# main_board.net
KiCad netlist of a schematic drawn in Altium Designer
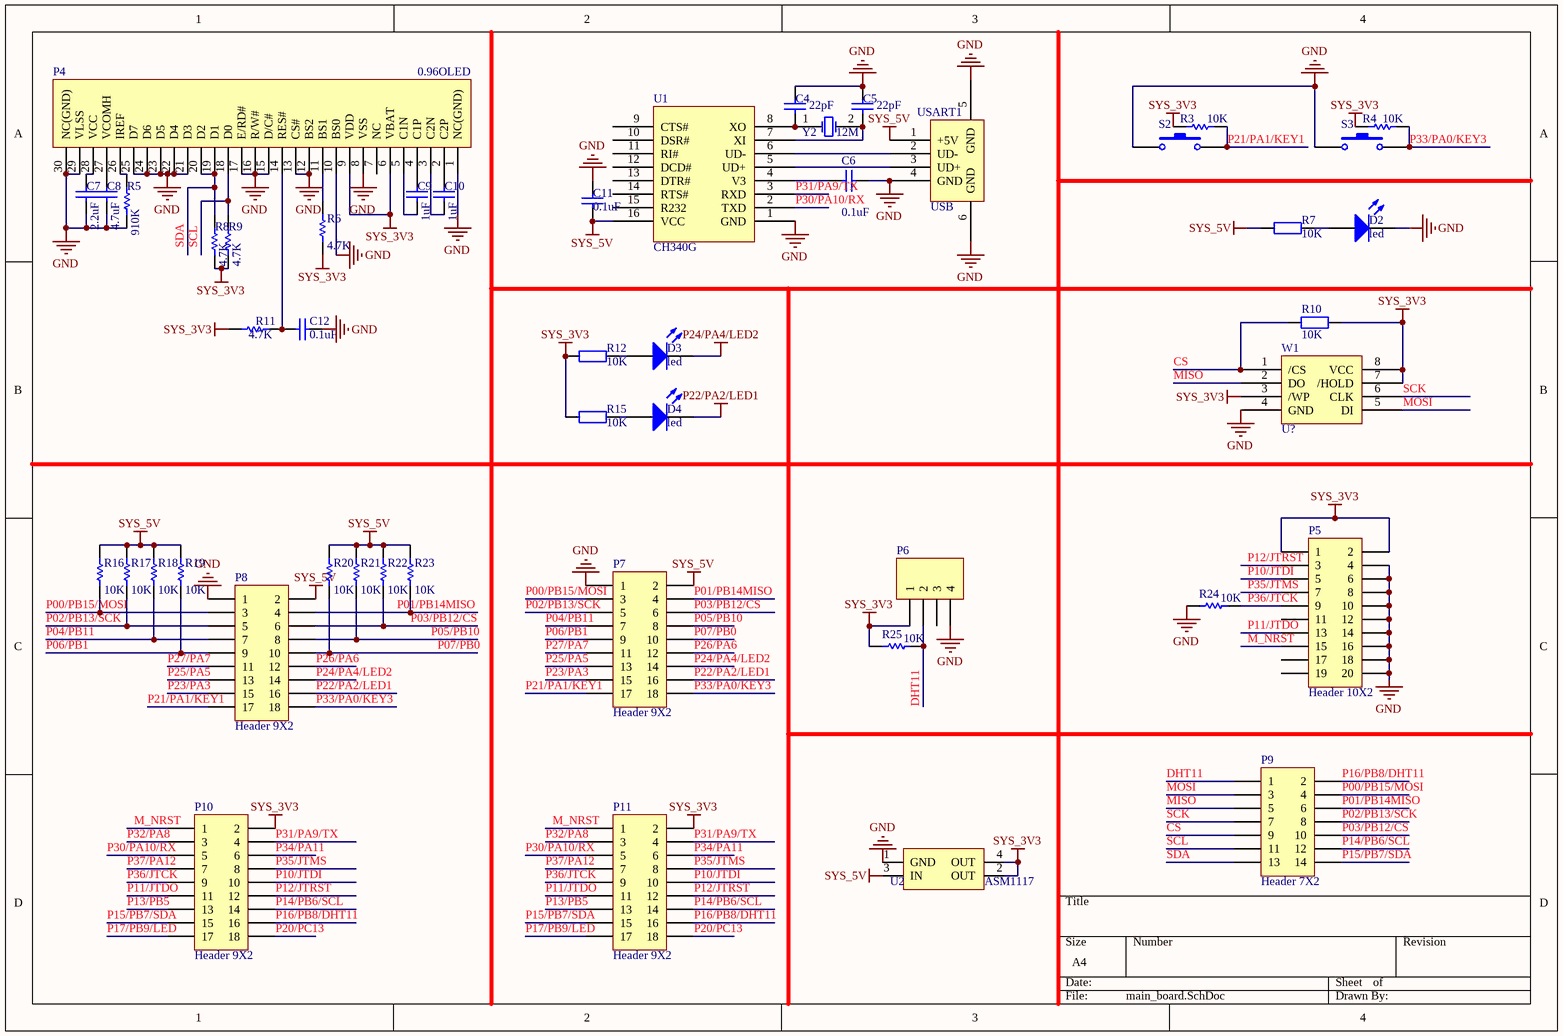
[diagram p0: main_board.SchDoc]

(export (version "E")
  (design (tool "Eeschema 10.0.6"))
  (components
    (comp (ref "C4")
      (value "22pF")
      (footprint "6-0805_N")
      (description "Capacitor")
      (fields (field (name "PUBLISHER") "Altium Limited"))
      (libsource (lib "Miscellaneous Devices") (part "Cap"))
    )
    (comp (ref "C5")
      (value "22pF")
      (footprint "6-0805_N")
      (description "Capacitor")
      (fields (field (name "PUBLISHER") "Altium Limited"))
      (libsource (lib "Miscellaneous Devices") (part "Cap"))
    )
    (comp (ref "C6")
      (value "0.1uF")
      (footprint "6-0805_N")
      (description "Capacitor")
      (fields (field (name "PUBLISHER") "Altium Limited"))
      (libsource (lib "Miscellaneous Devices") (part "Cap"))
    )
    (comp (ref "C7")
      (value "2.2uF")
      (footprint "6-0805_N")
      (description "Capacitor")
      (fields (field (name "PUBLISHER") "Altium Limited"))
      (libsource (lib "Miscellaneous Devices") (part "Cap"))
    )
    (comp (ref "C8")
      (value "4.7uF")
      (footprint "6-0805_N")
      (description "Capacitor")
      (fields (field (name "PUBLISHER") "Altium Limited"))
      (libsource (lib "Miscellaneous Devices") (part "Cap"))
    )
    (comp (ref "C9")
      (value "1uF")
      (footprint "6-0805_N")
      (description "Capacitor")
      (fields (field (name "PUBLISHER") "Altium Limited"))
      (libsource (lib "Miscellaneous Devices") (part "Cap"))
    )
    (comp (ref "C10")
      (value "1uF")
      (footprint "6-0805_N")
      (description "Capacitor")
      (fields (field (name "PUBLISHER") "Altium Limited"))
      (libsource (lib "Miscellaneous Devices") (part "Cap"))
    )
    (comp (ref "C11")
      (value "0.1uF")
      (footprint "6-0805_N")
      (description "Capacitor")
      (fields (field (name "PUBLISHER") "Altium Limited"))
      (libsource (lib "Miscellaneous Devices") (part "Cap"))
    )
    (comp (ref "C12")
      (value "0.1uF")
      (footprint "6-0805_N")
      (description "Capacitor")
      (fields (field (name "PUBLISHER") "Altium Limited"))
      (libsource (lib "Miscellaneous Devices") (part "Cap"))
    )
    (comp (ref "D2")
      (value "led")
      (footprint "LED")
      (description "Typical INFRARED GaAs LED")
      (fields (field (name "PUBLISHER") "Altium Limited"))
      (libsource (lib "Miscellaneous Devices") (part "LED0"))
    )
    (comp (ref "D3")
      (value "led")
      (footprint "LED")
      (description "Typical INFRARED GaAs LED")
      (fields (field (name "PUBLISHER") "Altium Limited"))
      (libsource (lib "Miscellaneous Devices") (part "LED0"))
    )
    (comp (ref "D4")
      (value "led")
      (footprint "LED")
      (description "Typical INFRARED GaAs LED")
      (fields (field (name "PUBLISHER") "Altium Limited"))
      (libsource (lib "Miscellaneous Devices") (part "LED0"))
    )
    (comp (ref "P4")
      (value "0.96OLED")
      (footprint "OLED")
      (description "接口")
      (fields (field (name "PUBLISHER") "Altium Limited"))
      (libsource (lib "HLW8012-Demo") (part "0.96OLED"))
    )
    (comp (ref "P5")
      (value "Header 10X2")
      (footprint "JLINK")
      (description "Header, 10-Pin, Dual row")
      (fields (field (name "PUBLISHER") "Altium Limited"))
      (libsource (lib "Miscellaneous Connectors") (part "Header 10X2"))
    )
    (comp (ref "P6")
      (value "~")
      (footprint "DHT11")
      (description "Header, 4-Pin")
      (fields (field (name "PUBLISHER") "Altium Limited"))
      (libsource (lib "Miscellaneous Connectors") (part "Header 4"))
    )
    (comp (ref "P7")
      (value "Header 9X2")
      (footprint "XDR2x9_L_1")
      (description "Header, 9-Pin, Dual row")
      (fields (field (name "PUBLISHER") "Altium Limited"))
      (libsource (lib "Miscellaneous Connectors") (part "Header 9X2"))
    )
    (comp (ref "P8")
      (value "Header 9X2")
      (footprint "XDR2x9_S")
      (description "Header, 9-Pin, Dual row")
      (fields (field (name "PUBLISHER") "Altium Limited"))
      (libsource (lib "Miscellaneous Connectors") (part "Header 9X2"))
    )
    (comp (ref "P9")
      (value "Header 7X2")
      (footprint "XDR2X7")
      (description "Header, 7-Pin, Dual row")
      (fields (field (name "PUBLISHER") "Altium Limited"))
      (libsource (lib "Miscellaneous Connectors") (part "Header 7X2"))
    )
    (comp (ref "P10")
      (value "Header 9X2")
      (footprint "XDR2x9_S")
      (description "Header, 9-Pin, Dual row")
      (fields (field (name "PUBLISHER") "Altium Limited"))
      (libsource (lib "Miscellaneous Connectors") (part "Header 9X2"))
    )
    (comp (ref "P11")
      (value "Header 9X2")
      (footprint "XDR2x9_L_2")
      (description "Header, 9-Pin, Dual row")
      (fields (field (name "PUBLISHER") "Altium Limited"))
      (libsource (lib "Miscellaneous Connectors") (part "Header 9X2"))
    )
    (comp (ref "R3")
      (value "10K")
      (footprint "6-0805_N")
      (description "Resistor")
      (fields (field (name "PUBLISHER") "Altium Limited"))
      (libsource (lib "Miscellaneous Devices") (part "Res1"))
    )
    (comp (ref "R4")
      (value "10K")
      (footprint "6-0805_N")
      (description "Resistor")
      (fields (field (name "PUBLISHER") "Altium Limited"))
      (libsource (lib "Miscellaneous Devices") (part "Res1"))
    )
    (comp (ref "R5")
      (value "910K")
      (footprint "6-0805_N")
      (description "Resistor")
      (fields (field (name "PUBLISHER") "Altium Limited"))
      (libsource (lib "Miscellaneous Devices") (part "Res1"))
    )
    (comp (ref "R6")
      (value "4.7K")
      (footprint "6-0805_N")
      (description "Resistor")
      (fields (field (name "PUBLISHER") "Altium Limited"))
      (libsource (lib "Miscellaneous Devices") (part "Res1"))
    )
    (comp (ref "R7")
      (value "10K")
      (footprint "6-0805_N")
      (description "Resistor")
      (fields (field (name "PUBLISHER") "Altium Limited"))
      (libsource (lib "Miscellaneous Devices") (part "Res2"))
    )
    (comp (ref "R8")
      (value "4.7K")
      (footprint "6-0805_N")
      (description "Resistor")
      (fields (field (name "PUBLISHER") "Altium Limited"))
      (libsource (lib "Miscellaneous Devices") (part "Res1"))
    )
    (comp (ref "R9")
      (value "4.7K")
      (footprint "6-0805_N")
      (description "Resistor")
      (fields (field (name "PUBLISHER") "Altium Limited"))
      (libsource (lib "Miscellaneous Devices") (part "Res1"))
    )
    (comp (ref "R10")
      (value "10K")
      (footprint "6-0805_N")
      (description "Resistor")
      (fields (field (name "PUBLISHER") "Altium Limited"))
      (libsource (lib "") (part "Res2_1"))
    )
    (comp (ref "R11")
      (value "4.7K")
      (footprint "6-0805_N")
      (description "Resistor")
      (fields (field (name "PUBLISHER") "Altium Limited"))
      (libsource (lib "Miscellaneous Devices") (part "Res1"))
    )
    (comp (ref "R12")
      (value "10K")
      (footprint "6-0805_N")
      (description "Resistor")
      (fields (field (name "PUBLISHER") "Altium Limited"))
      (libsource (lib "Miscellaneous Devices") (part "Res2"))
    )
    (comp (ref "R15")
      (value "10K")
      (footprint "6-0805_N")
      (description "Resistor")
      (fields (field (name "PUBLISHER") "Altium Limited"))
      (libsource (lib "Miscellaneous Devices") (part "Res2"))
    )
    (comp (ref "R16")
      (value "10K")
      (footprint "6-0805_N")
      (description "Resistor")
      (fields (field (name "PUBLISHER") "Altium Limited"))
      (libsource (lib "Miscellaneous Devices") (part "Res1"))
    )
    (comp (ref "R17")
      (value "10K")
      (footprint "6-0805_N")
      (description "Resistor")
      (fields (field (name "PUBLISHER") "Altium Limited"))
      (libsource (lib "Miscellaneous Devices") (part "Res1"))
    )
    (comp (ref "R18")
      (value "10K")
      (footprint "6-0805_N")
      (description "Resistor")
      (fields (field (name "PUBLISHER") "Altium Limited"))
      (libsource (lib "Miscellaneous Devices") (part "Res1"))
    )
    (comp (ref "R19")
      (value "10K")
      (footprint "6-0805_N")
      (description "Resistor")
      (fields (field (name "PUBLISHER") "Altium Limited"))
      (libsource (lib "Miscellaneous Devices") (part "Res1"))
    )
    (comp (ref "R20")
      (value "10K")
      (footprint "6-0805_N")
      (description "Resistor")
      (fields (field (name "PUBLISHER") "Altium Limited"))
      (libsource (lib "Miscellaneous Devices") (part "Res1"))
    )
    (comp (ref "R21")
      (value "10K")
      (footprint "6-0805_N")
      (description "Resistor")
      (fields (field (name "PUBLISHER") "Altium Limited"))
      (libsource (lib "Miscellaneous Devices") (part "Res1"))
    )
    (comp (ref "R22")
      (value "10K")
      (footprint "6-0805_N")
      (description "Resistor")
      (fields (field (name "PUBLISHER") "Altium Limited"))
      (libsource (lib "Miscellaneous Devices") (part "Res1"))
    )
    (comp (ref "R23")
      (value "10K")
      (footprint "6-0805_N")
      (description "Resistor")
      (fields (field (name "PUBLISHER") "Altium Limited"))
      (libsource (lib "Miscellaneous Devices") (part "Res1"))
    )
    (comp (ref "R24")
      (value "10K")
      (footprint "6-0805_N")
      (description "Resistor")
      (fields (field (name "PUBLISHER") "Altium Limited"))
      (libsource (lib "Miscellaneous Devices") (part "Res1"))
    )
    (comp (ref "R25")
      (value "10K")
      (footprint "6-0805_N")
      (description "Resistor")
      (fields (field (name "PUBLISHER") "Altium Limited"))
      (libsource (lib "Miscellaneous Devices") (part "Res1"))
    )
    (comp (ref "S2")
      (value "~")
      (footprint "SPST-2")
      (description "Switch")
      (fields (field (name "PUBLISHER") "Altium Limited"))
      (libsource (lib "Miscellaneous Devices") (part "SW-PB"))
    )
    (comp (ref "S3")
      (value "~")
      (footprint "SPST-2")
      (description "Switch")
      (fields (field (name "PUBLISHER") "Altium Limited"))
      (libsource (lib "Miscellaneous Devices") (part "SW-PB"))
    )
    (comp (ref "U1")
      (value "CH340G")
      (footprint "SOIC-16_150mil")
      (libsource (lib "Schlib1") (part "CH340G"))
    )
    (comp (ref "U2") (value "ASM1117") (footprint "SOT-223") (libsource (lib "BalanceCar") (part "ASM1117")))
    (comp (ref "USART1") (value "USB") (footprint "USB") (libsource (lib "Schlib1") (part "USB")))
    (comp (ref "W1") (value "U?") (footprint "SO8_N") (libsource (lib "One_Rice_DIY") (part "W25Q16")))
    (comp (ref "Y2")
      (value "12M")
      (footprint "HC-49S")
      (description "Crystal Oscillator")
      (fields (field (name "PUBLISHER") "Altium Limited"))
      (libsource (lib "Miscellaneous Devices") (part "XTAL"))
    )
  )
  (nets
    (net (code "1") (name "/CS") (class "Default")
      (node (ref "P9") (pin "9") (pinfunction "9_9") (pintype "passive"))
      (node (ref "R10") (pin "2") (pinfunction "2_2") (pintype "passive"))
      (node (ref "W1") (pin "1") (pinfunction "/CS_1") (pintype "passive"))
    )
    (net (code "2") (name "/DHT11") (class "Default")
      (node (ref "P6") (pin "2") (pinfunction "2_2") (pintype "passive"))
      (node (ref "P9") (pin "1") (pinfunction "1_1") (pintype "passive"))
      (node (ref "R25") (pin "2") (pinfunction "2_2") (pintype "passive"))
    )
    (net (code "3") (name "/MISO") (class "Default")
      (node (ref "P9") (pin "5") (pinfunction "5_5") (pintype "passive"))
      (node (ref "W1") (pin "2") (pinfunction "DO_2") (pintype "passive"))
    )
    (net (code "4") (name "/MOSI") (class "Default")
      (node (ref "P9") (pin "3") (pinfunction "3_3") (pintype "passive"))
      (node (ref "W1") (pin "5") (pinfunction "DI_5") (pintype "passive"))
    )
    (net (code "5") (name "/M_NRST") (class "Default")
      (node (ref "P10") (pin "1") (pinfunction "1_1") (pintype "passive"))
      (node (ref "P11") (pin "1") (pinfunction "1_1") (pintype "passive"))
      (node (ref "P5") (pin "15") (pinfunction "15_15") (pintype "passive"))
    )
    (net (code "6") (name "/P00{slash}PB15{slash}MOSI") (class "Default")
      (node (ref "P7") (pin "3") (pinfunction "3_3") (pintype "passive"))
      (node (ref "P8") (pin "3") (pinfunction "3_3") (pintype "passive"))
      (node (ref "P9") (pin "4") (pinfunction "4_4") (pintype "passive"))
      (node (ref "R16") (pin "1") (pinfunction "1_1") (pintype "passive"))
    )
    (net (code "7") (name "/P01{slash}PB14MISO") (class "Default")
      (node (ref "P7") (pin "4") (pinfunction "4_4") (pintype "passive"))
      (node (ref "P8") (pin "4") (pinfunction "4_4") (pintype "passive"))
      (node (ref "P9") (pin "6") (pinfunction "6_6") (pintype "passive"))
      (node (ref "R23") (pin "1") (pinfunction "1_1") (pintype "passive"))
    )
    (net (code "8") (name "/P02{slash}PB13{slash}SCK") (class "Default")
      (node (ref "P7") (pin "5") (pinfunction "5_5") (pintype "passive"))
      (node (ref "P8") (pin "5") (pinfunction "5_5") (pintype "passive"))
      (node (ref "P9") (pin "8") (pinfunction "8_8") (pintype "passive"))
      (node (ref "R17") (pin "1") (pinfunction "1_1") (pintype "passive"))
    )
    (net (code "9") (name "/P03{slash}PB12{slash}CS") (class "Default")
      (node (ref "P7") (pin "6") (pinfunction "6_6") (pintype "passive"))
      (node (ref "P8") (pin "6") (pinfunction "6_6") (pintype "passive"))
      (node (ref "P9") (pin "10") (pinfunction "10_10") (pintype "passive"))
      (node (ref "R22") (pin "1") (pinfunction "1_1") (pintype "passive"))
    )
    (net (code "10") (name "/P04{slash}PB11") (class "Default")
      (node (ref "P7") (pin "7") (pinfunction "7_7") (pintype "passive"))
      (node (ref "P8") (pin "7") (pinfunction "7_7") (pintype "passive"))
      (node (ref "R18") (pin "1") (pinfunction "1_1") (pintype "passive"))
    )
    (net (code "11") (name "/P05{slash}PB10") (class "Default")
      (node (ref "P7") (pin "8") (pinfunction "8_8") (pintype "passive"))
      (node (ref "P8") (pin "8") (pinfunction "8_8") (pintype "passive"))
      (node (ref "R21") (pin "1") (pinfunction "1_1") (pintype "passive"))
    )
    (net (code "12") (name "/P06{slash}PB1") (class "Default")
      (node (ref "P7") (pin "9") (pinfunction "9_9") (pintype "passive"))
      (node (ref "P8") (pin "9") (pinfunction "9_9") (pintype "passive"))
      (node (ref "R19") (pin "1") (pinfunction "1_1") (pintype "passive"))
    )
    (net (code "13") (name "/P07{slash}PB0") (class "Default")
      (node (ref "P7") (pin "10") (pinfunction "10_10") (pintype "passive"))
      (node (ref "P8") (pin "10") (pinfunction "10_10") (pintype "passive"))
      (node (ref "R20") (pin "1") (pinfunction "1_1") (pintype "passive"))
    )
    (net (code "14") (name "/P10{slash}JTDI") (class "Default")
      (node (ref "P10") (pin "10") (pinfunction "10_10") (pintype "passive"))
      (node (ref "P11") (pin "10") (pinfunction "10_10") (pintype "passive"))
      (node (ref "P5") (pin "5") (pinfunction "5_5") (pintype "passive"))
    )
    (net (code "15") (name "/P11{slash}JTDO") (class "Default")
      (node (ref "P10") (pin "11") (pinfunction "11_11") (pintype "passive"))
      (node (ref "P11") (pin "11") (pinfunction "11_11") (pintype "passive"))
      (node (ref "P5") (pin "13") (pinfunction "13_13") (pintype "passive"))
    )
    (net (code "16") (name "/P12{slash}JTRST") (class "Default")
      (node (ref "P10") (pin "12") (pinfunction "12_12") (pintype "passive"))
      (node (ref "P11") (pin "12") (pinfunction "12_12") (pintype "passive"))
      (node (ref "P5") (pin "3") (pinfunction "3_3") (pintype "passive"))
    )
    (net (code "17") (name "/P13{slash}PB5") (class "Default")
      (node (ref "P10") (pin "13") (pinfunction "13_13") (pintype "passive"))
      (node (ref "P11") (pin "13") (pinfunction "13_13") (pintype "passive"))
    )
    (net (code "18") (name "/P14{slash}PB6{slash}SCL") (class "Default")
      (node (ref "P10") (pin "14") (pinfunction "14_14") (pintype "passive"))
      (node (ref "P11") (pin "14") (pinfunction "14_14") (pintype "passive"))
      (node (ref "P9") (pin "12") (pinfunction "12_12") (pintype "passive"))
    )
    (net (code "19") (name "/P15{slash}PB7{slash}SDA") (class "Default")
      (node (ref "P10") (pin "15") (pinfunction "15_15") (pintype "passive"))
      (node (ref "P11") (pin "15") (pinfunction "15_15") (pintype "passive"))
      (node (ref "P9") (pin "14") (pinfunction "14_14") (pintype "passive"))
    )
    (net (code "20") (name "/P16{slash}PB8{slash}DHT11") (class "Default")
      (node (ref "P10") (pin "16") (pinfunction "16_16") (pintype "passive"))
      (node (ref "P11") (pin "16") (pinfunction "16_16") (pintype "passive"))
      (node (ref "P9") (pin "2") (pinfunction "2_2") (pintype "passive"))
    )
    (net (code "21") (name "/P17{slash}PB9{slash}LED") (class "Default")
      (node (ref "P10") (pin "17") (pinfunction "17_17") (pintype "passive"))
      (node (ref "P11") (pin "17") (pinfunction "17_17") (pintype "passive"))
    )
    (net (code "22") (name "/P20{slash}PC13") (class "Default")
      (node (ref "P10") (pin "18") (pinfunction "18_18") (pintype "passive"))
      (node (ref "P11") (pin "18") (pinfunction "18_18") (pintype "passive"))
    )
    (net (code "23") (name "/P21{slash}PA1{slash}KEY1") (class "Default")
      (node (ref "P7") (pin "17") (pinfunction "17_17") (pintype "passive"))
      (node (ref "P8") (pin "17") (pinfunction "17_17") (pintype "passive"))
      (node (ref "R3") (pin "1") (pinfunction "1_1") (pintype "passive"))
      (node (ref "S2") (pin "2") (pinfunction "2_2") (pintype "passive"))
    )
    (net (code "24") (name "/P23{slash}PA3") (class "Default")
      (node (ref "P7") (pin "15") (pinfunction "15_15") (pintype "passive"))
      (node (ref "P8") (pin "15") (pinfunction "15_15") (pintype "passive"))
    )
    (net (code "25") (name "/P25{slash}PA5") (class "Default")
      (node (ref "P7") (pin "13") (pinfunction "13_13") (pintype "passive"))
      (node (ref "P8") (pin "13") (pinfunction "13_13") (pintype "passive"))
    )
    (net (code "26") (name "/P26{slash}PA6") (class "Default")
      (node (ref "P7") (pin "12") (pinfunction "12_12") (pintype "passive"))
      (node (ref "P8") (pin "12") (pinfunction "12_12") (pintype "passive"))
    )
    (net (code "27") (name "/P27{slash}PA7") (class "Default")
      (node (ref "P7") (pin "11") (pinfunction "11_11") (pintype "passive"))
      (node (ref "P8") (pin "11") (pinfunction "11_11") (pintype "passive"))
    )
    (net (code "28") (name "/P30{slash}PA10{slash}RX") (class "Default")
      (node (ref "P10") (pin "5") (pinfunction "5_5") (pintype "passive"))
      (node (ref "P11") (pin "5") (pinfunction "5_5") (pintype "passive"))
      (node (ref "U1") (pin "2") (pinfunction "TXD_2") (pintype "passive"))
    )
    (net (code "29") (name "/P31{slash}PA9{slash}TX") (class "Default")
      (node (ref "P10") (pin "4") (pinfunction "4_4") (pintype "passive"))
      (node (ref "P11") (pin "4") (pinfunction "4_4") (pintype "passive"))
      (node (ref "U1") (pin "3") (pinfunction "RXD_3") (pintype "passive"))
    )
    (net (code "30") (name "/P32{slash}PA8") (class "Default")
      (node (ref "P10") (pin "3") (pinfunction "3_3") (pintype "passive"))
      (node (ref "P11") (pin "3") (pinfunction "3_3") (pintype "passive"))
    )
    (net (code "31") (name "/P33{slash}PA0{slash}KEY3") (class "Default")
      (node (ref "P7") (pin "18") (pinfunction "18_18") (pintype "passive"))
      (node (ref "P8") (pin "18") (pinfunction "18_18") (pintype "passive"))
      (node (ref "R4") (pin "1") (pinfunction "1_1") (pintype "passive"))
      (node (ref "S3") (pin "2") (pinfunction "2_2") (pintype "passive"))
    )
    (net (code "32") (name "/P34{slash}PA11") (class "Default")
      (node (ref "P10") (pin "6") (pinfunction "6_6") (pintype "passive"))
      (node (ref "P11") (pin "6") (pinfunction "6_6") (pintype "passive"))
    )
    (net (code "33") (name "/P35{slash}JTMS") (class "Default")
      (node (ref "P10") (pin "8") (pinfunction "8_8") (pintype "passive"))
      (node (ref "P11") (pin "8") (pinfunction "8_8") (pintype "passive"))
      (node (ref "P5") (pin "7") (pinfunction "7_7") (pintype "passive"))
    )
    (net (code "34") (name "/P36{slash}JTCK") (class "Default")
      (node (ref "P10") (pin "9") (pinfunction "9_9") (pintype "passive"))
      (node (ref "P11") (pin "9") (pinfunction "9_9") (pintype "passive"))
      (node (ref "P5") (pin "9") (pinfunction "9_9") (pintype "passive"))
      (node (ref "R24") (pin "2") (pinfunction "2_2") (pintype "passive"))
    )
    (net (code "35") (name "/P37{slash}PA12") (class "Default")
      (node (ref "P10") (pin "7") (pinfunction "7_7") (pintype "passive"))
      (node (ref "P11") (pin "7") (pinfunction "7_7") (pintype "passive"))
    )
    (net (code "36") (name "/SCK") (class "Default")
      (node (ref "P9") (pin "7") (pinfunction "7_7") (pintype "passive"))
      (node (ref "W1") (pin "6") (pinfunction "CLK_6") (pintype "passive"))
    )
    (net (code "37") (name "/SCL") (class "Default")
      (node (ref "P4") (pin "18") (pinfunction "D0_18") (pintype "passive"))
      (node (ref "P9") (pin "11") (pinfunction "11_11") (pintype "passive"))
      (node (ref "R9") (pin "1") (pinfunction "1_1") (pintype "passive"))
    )
    (net (code "38") (name "/SDA") (class "Default")
      (node (ref "P4") (pin "19") (pinfunction "D1_19") (pintype "passive"))
      (node (ref "P4") (pin "20") (pinfunction "D2_20") (pintype "passive"))
      (node (ref "P9") (pin "13") (pinfunction "13_13") (pintype "passive"))
      (node (ref "R8") (pin "1") (pinfunction "1_1") (pintype "passive"))
    )
    (net (code "39") (name "GND") (class "Default")
      (node (ref "C11") (pin "1") (pinfunction "1_1") (pintype "passive"))
      (node (ref "C12") (pin "1") (pinfunction "1_1") (pintype "passive"))
      (node (ref "C4") (pin "1") (pinfunction "1_1") (pintype "passive"))
      (node (ref "C5") (pin "1") (pinfunction "1_1") (pintype "passive"))
      (node (ref "C6") (pin "1") (pinfunction "1_1") (pintype "passive"))
      (node (ref "C7") (pin "1") (pinfunction "1_1") (pintype "passive"))
      (node (ref "C8") (pin "1") (pinfunction "1_1") (pintype "passive"))
      (node (ref "D2") (pin "2") (pinfunction "K_2") (pintype "passive"))
      (node (ref "P4") (pin "1") (pinfunction "NC(GND)_1") (pintype "passive"))
      (node (ref "P4") (pin "10") (pinfunction "BS0_10") (pintype "passive"))
      (node (ref "P4") (pin "12") (pinfunction "BS2_12") (pintype "passive"))
      (node (ref "P4") (pin "13") (pinfunction "CS#_13") (pintype "passive"))
      (node (ref "P4") (pin "15") (pinfunction "D/C#_15") (pintype "passive"))
      (node (ref "P4") (pin "16") (pinfunction "R/W#_16") (pintype "passive"))
      (node (ref "P4") (pin "17") (pinfunction "E/RD#_17") (pintype "passive"))
      (node (ref "P4") (pin "21") (pinfunction "D3_21") (pintype "passive"))
      (node (ref "P4") (pin "22") (pinfunction "D4_22") (pintype "passive"))
      (node (ref "P4") (pin "23") (pinfunction "D5_23") (pintype "passive"))
      (node (ref "P4") (pin "24") (pinfunction "D6_24") (pintype "passive"))
      (node (ref "P4") (pin "25") (pinfunction "D7_25") (pintype "passive"))
      (node (ref "P4") (pin "29") (pinfunction "VLSS_29") (pintype "passive"))
      (node (ref "P4") (pin "30") (pinfunction "NC(GND)_30") (pintype "passive"))
      (node (ref "P4") (pin "8") (pinfunction "VSS_8") (pintype "passive"))
      (node (ref "P5") (pin "10") (pinfunction "10_10") (pintype "passive"))
      (node (ref "P5") (pin "12") (pinfunction "12_12") (pintype "passive"))
      (node (ref "P5") (pin "14") (pinfunction "14_14") (pintype "passive"))
      (node (ref "P5") (pin "16") (pinfunction "16_16") (pintype "passive"))
      (node (ref "P5") (pin "18") (pinfunction "18_18") (pintype "passive"))
      (node (ref "P5") (pin "20") (pinfunction "20_20") (pintype "passive"))
      (node (ref "P5") (pin "4") (pinfunction "4_4") (pintype "passive"))
      (node (ref "P5") (pin "6") (pinfunction "6_6") (pintype "passive"))
      (node (ref "P5") (pin "8") (pinfunction "8_8") (pintype "passive"))
      (node (ref "P6") (pin "4") (pinfunction "4_4") (pintype "passive"))
      (node (ref "P7") (pin "1") (pinfunction "1_1") (pintype "passive"))
      (node (ref "P8") (pin "1") (pinfunction "1_1") (pintype "passive"))
      (node (ref "R24") (pin "1") (pinfunction "1_1") (pintype "passive"))
      (node (ref "R5") (pin "2") (pinfunction "2_2") (pintype "passive"))
      (node (ref "S2") (pin "1") (pinfunction "1_1") (pintype "passive"))
      (node (ref "S3") (pin "1") (pinfunction "1_1") (pintype "passive"))
      (node (ref "U1") (pin "1") (pinfunction "GND_1") (pintype "passive"))
      (node (ref "U2") (pin "1") (pinfunction "GND_1") (pintype "passive"))
      (node (ref "USART1") (pin "4") (pinfunction "GND_4") (pintype "passive"))
      (node (ref "USART1") (pin "5") (pinfunction "GND_5") (pintype "passive"))
      (node (ref "USART1") (pin "6") (pinfunction "GND_6") (pintype "passive"))
      (node (ref "W1") (pin "4") (pinfunction "GND_4") (pintype "passive"))
    )
    (net (code "40") (name "Net-(D2-A)") (class "Default")
      (node (ref "D2") (pin "1") (pinfunction "A_1") (pintype "passive"))
      (node (ref "R7") (pin "2") (pinfunction "2_2") (pintype "passive"))
    )
    (net (code "41") (name "Net-(D3-A)") (class "Default")
      (node (ref "D3") (pin "1") (pinfunction "A_1") (pintype "passive"))
      (node (ref "R12") (pin "2") (pinfunction "2_2") (pintype "passive"))
    )
    (net (code "42") (name "Net-(D4-A)") (class "Default")
      (node (ref "D4") (pin "1") (pinfunction "A_1") (pintype "passive"))
      (node (ref "R15") (pin "2") (pinfunction "2_2") (pintype "passive"))
    )
    (net (code "43") (name "Net-(P4-BS1)") (class "Default")
      (node (ref "P4") (pin "11") (pinfunction "BS1_11") (pintype "passive"))
      (node (ref "R6") (pin "2") (pinfunction "2_2") (pintype "passive"))
    )
    (net (code "44") (name "Net-(P4-C1N)") (class "Default")
      (node (ref "C9") (pin "1") (pinfunction "1_1") (pintype "passive"))
      (node (ref "P4") (pin "5") (pinfunction "C1N_5") (pintype "passive"))
    )
    (net (code "45") (name "Net-(P4-C1P)") (class "Default")
      (node (ref "C9") (pin "2") (pinfunction "2_2") (pintype "passive"))
      (node (ref "P4") (pin "4") (pinfunction "C1P_4") (pintype "passive"))
    )
    (net (code "46") (name "Net-(P4-C2N)") (class "Default")
      (node (ref "C10") (pin "1") (pinfunction "1_1") (pintype "passive"))
      (node (ref "P4") (pin "3") (pinfunction "C2N_3") (pintype "passive"))
    )
    (net (code "47") (name "Net-(P4-C2P)") (class "Default")
      (node (ref "C10") (pin "2") (pinfunction "2_2") (pintype "passive"))
      (node (ref "P4") (pin "2") (pinfunction "C2P_2") (pintype "passive"))
    )
    (net (code "48") (name "Net-(P4-IREF)") (class "Default")
      (node (ref "P4") (pin "26") (pinfunction "IREF_26") (pintype "passive"))
      (node (ref "R5") (pin "1") (pinfunction "1_1") (pintype "passive"))
    )
    (net (code "49") (name "Net-(P4-RES#)") (class "Default")
      (node (ref "C12") (pin "2") (pinfunction "2_2") (pintype "passive"))
      (node (ref "P4") (pin "14") (pinfunction "RES#_14") (pintype "passive"))
      (node (ref "R11") (pin "2") (pinfunction "2_2") (pintype "passive"))
    )
    (net (code "50") (name "Net-(P4-VCC)") (class "Default")
      (node (ref "C7") (pin "2") (pinfunction "2_2") (pintype "passive"))
      (node (ref "P4") (pin "28") (pinfunction "VCC_28") (pintype "passive"))
    )
    (net (code "51") (name "Net-(P4-VCOMH)") (class "Default")
      (node (ref "C8") (pin "2") (pinfunction "2_2") (pintype "passive"))
      (node (ref "P4") (pin "27") (pinfunction "VCOMH_27") (pintype "passive"))
    )
    (net (code "52") (name "Net-(U1-UD+)") (class "Default")
      (node (ref "U1") (pin "5") (pinfunction "UD+_5") (pintype "passive"))
      (node (ref "USART1") (pin "3") (pinfunction "UD+_3") (pintype "passive"))
    )
    (net (code "53") (name "Net-(U1-UD-)") (class "Default")
      (node (ref "U1") (pin "6") (pinfunction "UD-_6") (pintype "passive"))
      (node (ref "USART1") (pin "2") (pinfunction "UD-_2") (pintype "passive"))
    )
    (net (code "54") (name "Net-(U1-V3)") (class "Default")
      (node (ref "C6") (pin "2") (pinfunction "2_2") (pintype "passive"))
      (node (ref "U1") (pin "4") (pinfunction "V3_4") (pintype "passive"))
    )
    (net (code "55") (name "Net-(U1-XI)") (class "Default")
      (node (ref "C5") (pin "2") (pinfunction "2_2") (pintype "passive"))
      (node (ref "U1") (pin "7") (pinfunction "XI_7") (pintype "passive"))
      (node (ref "Y2") (pin "2") (pinfunction "OSC2_2") (pintype "passive"))
    )
    (net (code "56") (name "Net-(U1-XO)") (class "Default")
      (node (ref "C4") (pin "2") (pinfunction "2_2") (pintype "passive"))
      (node (ref "U1") (pin "8") (pinfunction "XO_8") (pintype "passive"))
      (node (ref "Y2") (pin "1") (pinfunction "OSC1_1") (pintype "passive"))
    )
    (net (code "57") (name "P22{slash}PA2{slash}LED1") (class "Default")
      (node (ref "D4") (pin "2") (pinfunction "K_2") (pintype "passive"))
      (node (ref "P7") (pin "16") (pinfunction "16_16") (pintype "passive"))
      (node (ref "P8") (pin "16") (pinfunction "16_16") (pintype "passive"))
    )
    (net (code "58") (name "P24{slash}PA4{slash}LED2") (class "Default")
      (node (ref "D3") (pin "2") (pinfunction "K_2") (pintype "passive"))
      (node (ref "P7") (pin "14") (pinfunction "14_14") (pintype "passive"))
      (node (ref "P8") (pin "14") (pinfunction "14_14") (pintype "passive"))
    )
    (net (code "59") (name "SYS_3V3") (class "Default")
      (node (ref "P10") (pin "2") (pinfunction "2_2") (pintype "passive"))
      (node (ref "P11") (pin "2") (pinfunction "2_2") (pintype "passive"))
      (node (ref "P4") (pin "6") (pinfunction "VBAT_6") (pintype "passive"))
      (node (ref "P4") (pin "9") (pinfunction "VDD_9") (pintype "passive"))
      (node (ref "P5") (pin "1") (pinfunction "1_1") (pintype "passive"))
      (node (ref "P5") (pin "2") (pinfunction "2_2") (pintype "passive"))
      (node (ref "P6") (pin "1") (pinfunction "1_1") (pintype "passive"))
      (node (ref "R10") (pin "1") (pinfunction "1_1") (pintype "passive"))
      (node (ref "R11") (pin "1") (pinfunction "1_1") (pintype "passive"))
      (node (ref "R12") (pin "1") (pinfunction "1_1") (pintype "passive"))
      (node (ref "R15") (pin "1") (pinfunction "1_1") (pintype "passive"))
      (node (ref "R25") (pin "1") (pinfunction "1_1") (pintype "passive"))
      (node (ref "R3") (pin "2") (pinfunction "2_2") (pintype "passive"))
      (node (ref "R4") (pin "2") (pinfunction "2_2") (pintype "passive"))
      (node (ref "R6") (pin "1") (pinfunction "1_1") (pintype "passive"))
      (node (ref "R8") (pin "2") (pinfunction "2_2") (pintype "passive"))
      (node (ref "R9") (pin "2") (pinfunction "2_2") (pintype "passive"))
      (node (ref "U2") (pin "2") (pinfunction "OUT_2") (pintype "passive"))
      (node (ref "U2") (pin "4") (pinfunction "OUT_4") (pintype "passive"))
      (node (ref "W1") (pin "3") (pinfunction "/WP_3") (pintype "passive"))
      (node (ref "W1") (pin "7") (pinfunction "/HOLD_7") (pintype "passive"))
      (node (ref "W1") (pin "8") (pinfunction "VCC_8") (pintype "passive"))
    )
    (net (code "60") (name "SYS_5V") (class "Default")
      (node (ref "C11") (pin "2") (pinfunction "2_2") (pintype "passive"))
      (node (ref "P7") (pin "2") (pinfunction "2_2") (pintype "passive"))
      (node (ref "P8") (pin "2") (pinfunction "2_2") (pintype "passive"))
      (node (ref "R16") (pin "2") (pinfunction "2_2") (pintype "passive"))
      (node (ref "R17") (pin "2") (pinfunction "2_2") (pintype "passive"))
      (node (ref "R18") (pin "2") (pinfunction "2_2") (pintype "passive"))
      (node (ref "R19") (pin "2") (pinfunction "2_2") (pintype "passive"))
      (node (ref "R20") (pin "2") (pinfunction "2_2") (pintype "passive"))
      (node (ref "R21") (pin "2") (pinfunction "2_2") (pintype "passive"))
      (node (ref "R22") (pin "2") (pinfunction "2_2") (pintype "passive"))
      (node (ref "R23") (pin "2") (pinfunction "2_2") (pintype "passive"))
      (node (ref "R7") (pin "1") (pinfunction "1_1") (pintype "passive"))
      (node (ref "U1") (pin "16") (pinfunction "VCC_16") (pintype "passive"))
      (node (ref "U2") (pin "3") (pinfunction "IN_3") (pintype "passive"))
      (node (ref "USART1") (pin "1") (pinfunction "+5V_1") (pintype "passive"))
    )
    (net (code "61") (name "unconnected-(P4-NC-Pad7)") (class "Default")
      (node (ref "P4") (pin "7") (pinfunction "NC_7") (pintype "passive"))
    )
    (net (code "62") (name "unconnected-(P5-Pad11)") (class "Default")
      (node (ref "P5") (pin "11") (pinfunction "11_11") (pintype "passive"))
    )
    (net (code "63") (name "unconnected-(P5-Pad17)") (class "Default")
      (node (ref "P5") (pin "17") (pinfunction "17_17") (pintype "passive"))
    )
    (net (code "64") (name "unconnected-(P5-Pad19)") (class "Default")
      (node (ref "P5") (pin "19") (pinfunction "19_19") (pintype "passive"))
    )
    (net (code "65") (name "unconnected-(P6-Pad3)") (class "Default")
      (node (ref "P6") (pin "3") (pinfunction "3_3") (pintype "passive"))
    )
    (net (code "66") (name "unconnected-(U1-CTS#-Pad9)") (class "Default")
      (node (ref "U1") (pin "9") (pinfunction "CTS#_9") (pintype "passive"))
    )
    (net (code "67") (name "unconnected-(U1-DCD#-Pad12)") (class "Default")
      (node (ref "U1") (pin "12") (pinfunction "DCD#_12") (pintype "passive"))
    )
    (net (code "68") (name "unconnected-(U1-DSR#-Pad10)") (class "Default")
      (node (ref "U1") (pin "10") (pinfunction "DSR#_10") (pintype "passive"))
    )
    (net (code "69") (name "unconnected-(U1-DTR#-Pad13)") (class "Default")
      (node (ref "U1") (pin "13") (pinfunction "DTR#_13") (pintype "passive"))
    )
    (net (code "70") (name "unconnected-(U1-R232-Pad15)") (class "Default")
      (node (ref "U1") (pin "15") (pinfunction "R232_15") (pintype "passive"))
    )
    (net (code "71") (name "unconnected-(U1-RI#-Pad11)") (class "Default")
      (node (ref "U1") (pin "11") (pinfunction "RI#_11") (pintype "passive"))
    )
    (net (code "72") (name "unconnected-(U1-RTS#-Pad14)") (class "Default")
      (node (ref "U1") (pin "14") (pinfunction "RTS#_14") (pintype "passive"))
    )
  )
)
